# LowduinoPTH_v2.net
KiCad netlist of a schematic drawn in EAGLE
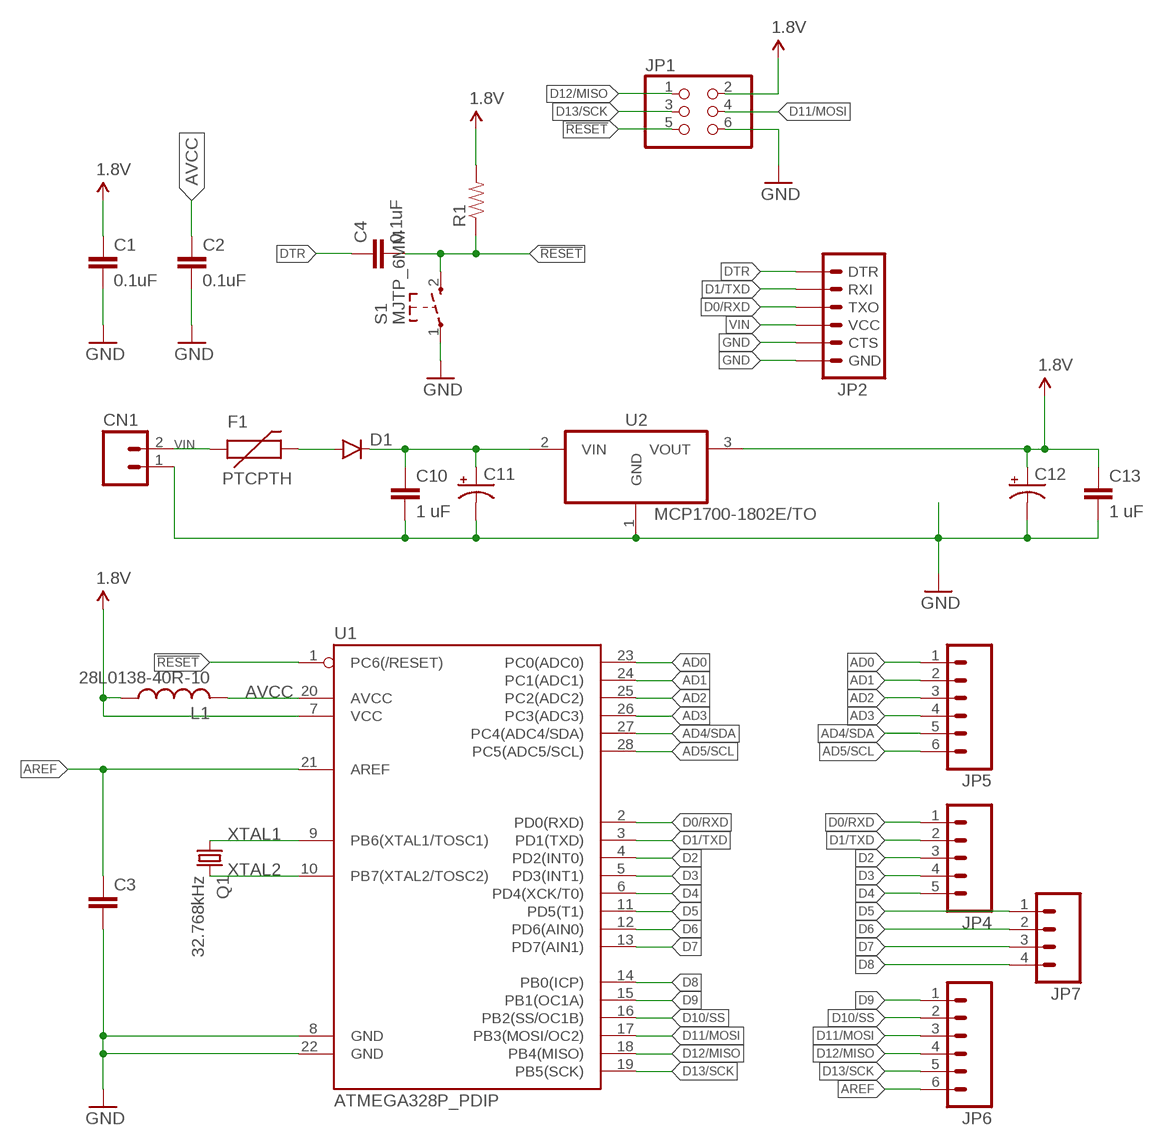
[diagram p0: schematic, sheet 1]

(export (version "E")
  (design (tool "Eeschema 10.0.6"))
  (components
    (comp (ref "C1")
      (value "0.1uF")
      (footprint "eagle-import:CAP-PTH-SMALL")
      (libsource (lib "eagle-import") (part "CAPPTH"))
    )
    (comp (ref "C2")
      (value "0.1uF")
      (footprint "eagle-import:CAP-PTH-5MM")
      (libsource (lib "eagle-import") (part "SparkFun-Passives_CAPPTH1"))
    )
    (comp (ref "C3")
      (value "CAPPTH")
      (footprint "eagle-import:CAP-PTH-SMALL")
      (libsource (lib "eagle-import") (part "CAPPTH"))
    )
    (comp (ref "C4")
      (value "0.1uF")
      (footprint "eagle-import:CAP-PTH-SMALL")
      (libsource (lib "eagle-import") (part "CAPPTH"))
    )
    (comp (ref "C10")
      (value "1 uF")
      (footprint "eagle-import:CAP-PTH-SMALL")
      (libsource (lib "eagle-import") (part "CAPPTH"))
    )
    (comp (ref "C11")
      (value "CPOL-USE2.5-6")
      (footprint "eagle-import:E2,5-6")
      (libsource (lib "eagle-import") (part "CPOL-USE2.5-6"))
    )
    (comp (ref "C12")
      (value "CPOL-USE2.5-6")
      (footprint "eagle-import:E2,5-6")
      (libsource (lib "eagle-import") (part "CPOL-USE2.5-6"))
    )
    (comp (ref "C13")
      (value "1 uF")
      (footprint "eagle-import:CAP-PTH-SMALL")
      (libsource (lib "eagle-import") (part "CAPPTH"))
    )
    (comp (ref "CN1")
      (value "M02JST-PTH-VERT")
      (footprint "eagle-import:JST-2-PTH-VERT")
      (libsource (lib "eagle-import") (part "M02JST-PTH-VERT"))
    )
    (comp (ref "D1")
      (value "DIODEPTH")
      (footprint "eagle-import:DIODE-1N4001")
      (libsource (lib "eagle-import") (part "DIODEPTH"))
    )
    (comp (ref "F1")
      (value "PTCPTH")
      (footprint "eagle-import:PTC")
      (libsource (lib "eagle-import") (part "PTCPTH"))
    )
    (comp (ref "JP1")
      (value "PINHD-2X3")
      (footprint "eagle-import:2X03")
      (libsource (lib "eagle-import") (part "PINHD-2X3"))
    )
    (comp (ref "JP2")
      (value "ARDUINO_SERIAL_PROGRAMPTH")
      (footprint "eagle-import:1X06")
      (libsource (lib "eagle-import") (part "ARDUINO_SERIAL_PROGRAMPTH"))
    )
    (comp (ref "JP4")
      (value "M05NO_SILK")
      (footprint "eagle-import:1X05_NO_SILK")
      (libsource (lib "eagle-import") (part "M05NO_SILK"))
    )
    (comp (ref "JP5")
      (value "M06NO_SILK_FEMALE_PTH")
      (footprint "eagle-import:1X06_NO_SILK")
      (libsource (lib "eagle-import") (part "M06NO_SILK_FEMALE_PTH"))
    )
    (comp (ref "JP6")
      (value "M06NO_SILK_FEMALE_PTH")
      (footprint "eagle-import:1X06_NO_SILK")
      (libsource (lib "eagle-import") (part "M06NO_SILK_FEMALE_PTH"))
    )
    (comp (ref "JP7")
      (value "M04NO_SILK_ALL_ROUND")
      (footprint "eagle-import:1X04_NO_SILK_ALL_ROUND")
      (libsource (lib "eagle-import") (part "M04NO_SILK_ALL_ROUND"))
    )
    (comp (ref "L1")
      (value "28L0138-40R-10")
      (footprint "eagle-import:LAL03")
      (libsource (lib "eagle-import") (part "L-USLAL03"))
    )
    (comp (ref "Q1")
      (value "32.768kHz")
      (footprint "eagle-import:TC26V")
      (libsource (lib "eagle-import") (part "CRYSTALTC26V"))
    )
    (comp (ref "R1")
      (value "RESISTORPTH-1/4W-VERT")
      (footprint "eagle-import:AXIAL-0.1")
      (libsource (lib "eagle-import") (part "RESISTORPTH-1/4W-VERT"))
    )
    (comp (ref "S1")
      (value "MJTP_6MM")
      (footprint "eagle-import:MJTP1243")
      (libsource (lib "eagle-import") (part "MJTP_6MM"))
    )
    (comp (ref "U1")
      (value "ATMEGA328P_PDIP")
      (footprint "eagle-import:DIL28-3")
      (libsource (lib "eagle-import") (part "ATMEGA328P_PDIP"))
    )
    (comp (ref "U2")
      (value "MCP1700-1802E/TO")
      (footprint "eagle-import:MICROCHIP_TO")
      (libsource (lib "eagle-import") (part "MCP1700TO-1802E/"))
    )
  )
  (nets
    (net (code "1") (name "/XTAL1") (class "Default")
      (node (ref "Q1") (pin "1") (pinfunction "1_1") (pintype "passive"))
      (node (ref "U1") (pin "9") (pinfunction "PB6(XTAL1/TOSC1)_9") (pintype "bidirectional"))
    )
    (net (code "2") (name "/XTAL2") (class "Default")
      (node (ref "Q1") (pin "2") (pinfunction "2_2") (pintype "passive"))
      (node (ref "U1") (pin "10") (pinfunction "PB7(XTAL2/TOSC2)_10") (pintype "bidirectional"))
    )
    (net (code "3") (name "/~{RESET}") (class "Default")
      (node (ref "C4") (pin "2") (pinfunction "2_2") (pintype "passive"))
      (node (ref "JP1") (pin "5") (pinfunction "5_5") (pintype "passive"))
      (node (ref "R1") (pin "P$1") (pinfunction "1_P$1") (pintype "passive"))
      (node (ref "S1") (pin "2") (pinfunction "3_2") (pintype "passive"))
      (node (ref "U1") (pin "1") (pinfunction "PC6(/RESET)_1") (pintype "bidirectional"))
    )
    (net (code "4") (name "1.8V") (class "Default")
      (node (ref "C1") (pin "1") (pinfunction "1_1") (pintype "passive"))
      (node (ref "C12") (pin "+") (pinfunction "+_+") (pintype "passive"))
      (node (ref "C13") (pin "1") (pinfunction "1_1") (pintype "passive"))
      (node (ref "JP1") (pin "2") (pinfunction "2_2") (pintype "passive"))
      (node (ref "L1") (pin "1") (pinfunction "1_1") (pintype "passive"))
      (node (ref "R1") (pin "P$2") (pinfunction "2_P$2") (pintype "passive"))
      (node (ref "U1") (pin "7") (pinfunction "VCC_7") (pintype "bidirectional"))
      (node (ref "U2") (pin "3") (pinfunction "VOUT_3") (pintype "output"))
    )
    (net (code "5") (name "AD0") (class "Default")
      (node (ref "JP5") (pin "1") (pinfunction "1_1") (pintype "passive"))
      (node (ref "U1") (pin "23") (pinfunction "PC0(ADC0)_23") (pintype "bidirectional"))
    )
    (net (code "6") (name "AD1") (class "Default")
      (node (ref "JP5") (pin "2") (pinfunction "2_2") (pintype "passive"))
      (node (ref "U1") (pin "24") (pinfunction "PC1(ADC1)_24") (pintype "bidirectional"))
    )
    (net (code "7") (name "AD2") (class "Default")
      (node (ref "JP5") (pin "3") (pinfunction "3_3") (pintype "passive"))
      (node (ref "U1") (pin "25") (pinfunction "PC2(ADC2)_25") (pintype "bidirectional"))
    )
    (net (code "8") (name "AD3") (class "Default")
      (node (ref "JP5") (pin "4") (pinfunction "4_4") (pintype "passive"))
      (node (ref "U1") (pin "26") (pinfunction "PC3(ADC3)_26") (pintype "bidirectional"))
    )
    (net (code "9") (name "AD4{slash}SDA") (class "Default")
      (node (ref "JP5") (pin "5") (pinfunction "5_5") (pintype "passive"))
      (node (ref "U1") (pin "27") (pinfunction "PC4(ADC4/SDA)_27") (pintype "bidirectional"))
    )
    (net (code "10") (name "AD5{slash}SCL") (class "Default")
      (node (ref "JP5") (pin "6") (pinfunction "6_6") (pintype "passive"))
      (node (ref "U1") (pin "28") (pinfunction "PC5(ADC5/SCL)_28") (pintype "bidirectional"))
    )
    (net (code "11") (name "AREF") (class "Default")
      (node (ref "C3") (pin "1") (pinfunction "1_1") (pintype "passive"))
      (node (ref "JP6") (pin "6") (pinfunction "6_6") (pintype "passive"))
      (node (ref "U1") (pin "21") (pinfunction "AREF_21") (pintype "bidirectional"))
    )
    (net (code "12") (name "AVCC") (class "Default")
      (node (ref "C2") (pin "1") (pinfunction "1_1") (pintype "passive"))
      (node (ref "L1") (pin "2") (pinfunction "2_2") (pintype "passive"))
      (node (ref "U1") (pin "20") (pinfunction "AVCC_20") (pintype "bidirectional"))
    )
    (net (code "13") (name "D0{slash}RXD") (class "Default")
      (node (ref "JP2") (pin "3") (pinfunction "TXO_3") (pintype "passive"))
      (node (ref "JP4") (pin "1") (pinfunction "1_1") (pintype "passive"))
      (node (ref "U1") (pin "2") (pinfunction "PD0(RXD)_2") (pintype "bidirectional"))
    )
    (net (code "14") (name "D1{slash}TXD") (class "Default")
      (node (ref "JP2") (pin "2") (pinfunction "RXI_2") (pintype "passive"))
      (node (ref "JP4") (pin "2") (pinfunction "2_2") (pintype "passive"))
      (node (ref "U1") (pin "3") (pinfunction "PD1(TXD)_3") (pintype "bidirectional"))
    )
    (net (code "15") (name "D2") (class "Default")
      (node (ref "JP4") (pin "3") (pinfunction "3_3") (pintype "passive"))
      (node (ref "U1") (pin "4") (pinfunction "PD2(INT0)_4") (pintype "bidirectional"))
    )
    (net (code "16") (name "D3") (class "Default")
      (node (ref "JP4") (pin "4") (pinfunction "4_4") (pintype "passive"))
      (node (ref "U1") (pin "5") (pinfunction "PD3(INT1)_5") (pintype "bidirectional"))
    )
    (net (code "17") (name "D4") (class "Default")
      (node (ref "JP4") (pin "5") (pinfunction "5_5") (pintype "passive"))
      (node (ref "U1") (pin "6") (pinfunction "PD4(XCK/T0)_6") (pintype "bidirectional"))
    )
    (net (code "18") (name "D5") (class "Default")
      (node (ref "JP7") (pin "1") (pinfunction "1_1") (pintype "passive"))
      (node (ref "U1") (pin "11") (pinfunction "PD5(T1)_11") (pintype "bidirectional"))
    )
    (net (code "19") (name "D6") (class "Default")
      (node (ref "JP7") (pin "2") (pinfunction "2_2") (pintype "passive"))
      (node (ref "U1") (pin "12") (pinfunction "PD6(AIN0)_12") (pintype "bidirectional"))
    )
    (net (code "20") (name "D7") (class "Default")
      (node (ref "JP7") (pin "3") (pinfunction "3_3") (pintype "passive"))
      (node (ref "U1") (pin "13") (pinfunction "PD7(AIN1)_13") (pintype "bidirectional"))
    )
    (net (code "21") (name "D8") (class "Default")
      (node (ref "JP7") (pin "4") (pinfunction "4_4") (pintype "passive"))
      (node (ref "U1") (pin "14") (pinfunction "PB0(ICP)_14") (pintype "bidirectional"))
    )
    (net (code "22") (name "D9") (class "Default")
      (node (ref "JP6") (pin "1") (pinfunction "1_1") (pintype "passive"))
      (node (ref "U1") (pin "15") (pinfunction "PB1(OC1A)_15") (pintype "bidirectional"))
    )
    (net (code "23") (name "D10{slash}SS") (class "Default")
      (node (ref "JP6") (pin "2") (pinfunction "2_2") (pintype "passive"))
      (node (ref "U1") (pin "16") (pinfunction "PB2(SS/OC1B)_16") (pintype "bidirectional"))
    )
    (net (code "24") (name "D11{slash}MOSI") (class "Default")
      (node (ref "JP1") (pin "4") (pinfunction "4_4") (pintype "passive"))
      (node (ref "JP6") (pin "3") (pinfunction "3_3") (pintype "passive"))
      (node (ref "U1") (pin "17") (pinfunction "PB3(MOSI/OC2)_17") (pintype "bidirectional"))
    )
    (net (code "25") (name "D12{slash}MISO") (class "Default")
      (node (ref "JP1") (pin "1") (pinfunction "1_1") (pintype "passive"))
      (node (ref "JP6") (pin "4") (pinfunction "4_4") (pintype "passive"))
      (node (ref "U1") (pin "18") (pinfunction "PB4(MISO)_18") (pintype "bidirectional"))
    )
    (net (code "26") (name "D13{slash}SCK") (class "Default")
      (node (ref "JP1") (pin "3") (pinfunction "3_3") (pintype "passive"))
      (node (ref "JP6") (pin "5") (pinfunction "5_5") (pintype "passive"))
      (node (ref "U1") (pin "19") (pinfunction "PB5(SCK)_19") (pintype "bidirectional"))
    )
    (net (code "27") (name "DTR") (class "Default")
      (node (ref "C4") (pin "1") (pinfunction "1_1") (pintype "passive"))
      (node (ref "JP2") (pin "1") (pinfunction "DTR_1") (pintype "passive"))
    )
    (net (code "28") (name "GND") (class "Default")
      (node (ref "C1") (pin "2") (pinfunction "2_2") (pintype "passive"))
      (node (ref "C10") (pin "2") (pinfunction "2_2") (pintype "passive"))
      (node (ref "C11") (pin "-") (pinfunction "-_-") (pintype "passive"))
      (node (ref "C12") (pin "-") (pinfunction "-_-") (pintype "passive"))
      (node (ref "C13") (pin "2") (pinfunction "2_2") (pintype "passive"))
      (node (ref "C2") (pin "2") (pinfunction "2_2") (pintype "passive"))
      (node (ref "C3") (pin "2") (pinfunction "2_2") (pintype "passive"))
      (node (ref "CN1") (pin "1") (pinfunction "1_1") (pintype "passive"))
      (node (ref "JP1") (pin "6") (pinfunction "6_6") (pintype "passive"))
      (node (ref "JP2") (pin "5") (pinfunction "CTS_5") (pintype "passive"))
      (node (ref "JP2") (pin "6") (pinfunction "GND_6") (pintype "passive"))
      (node (ref "S1") (pin "1") (pinfunction "1_1") (pintype "passive"))
      (node (ref "U1") (pin "22") (pinfunction "GND_22") (pintype "bidirectional"))
      (node (ref "U1") (pin "8") (pinfunction "GND_8") (pintype "bidirectional"))
      (node (ref "U2") (pin "1") (pinfunction "GND_1") (pintype "passive"))
    )
    (net (code "29") (name "Net-(F1-2)") (class "Default")
      (node (ref "D1") (pin "A") (pinfunction "A_A") (pintype "passive"))
      (node (ref "F1") (pin "P$2") (pinfunction "2_P$2") (pintype "bidirectional"))
    )
    (net (code "30") (name "Net-(U2-VIN)") (class "Default")
      (node (ref "C10") (pin "1") (pinfunction "1_1") (pintype "passive"))
      (node (ref "C11") (pin "+") (pinfunction "+_+") (pintype "passive"))
      (node (ref "D1") (pin "C") (pinfunction "C_C") (pintype "passive"))
      (node (ref "U2") (pin "2") (pinfunction "VIN_2") (pintype "input"))
    )
    (net (code "31") (name "VIN") (class "Default")
      (node (ref "CN1") (pin "2") (pinfunction "2_2") (pintype "passive"))
      (node (ref "F1") (pin "P$1") (pinfunction "1_P$1") (pintype "bidirectional"))
      (node (ref "JP2") (pin "4") (pinfunction "VCC_4") (pintype "passive"))
    )
  )
)
